# ESP32-S2_VoiceModulator.net
KiCad netlist of a schematic drawn in EAGLE
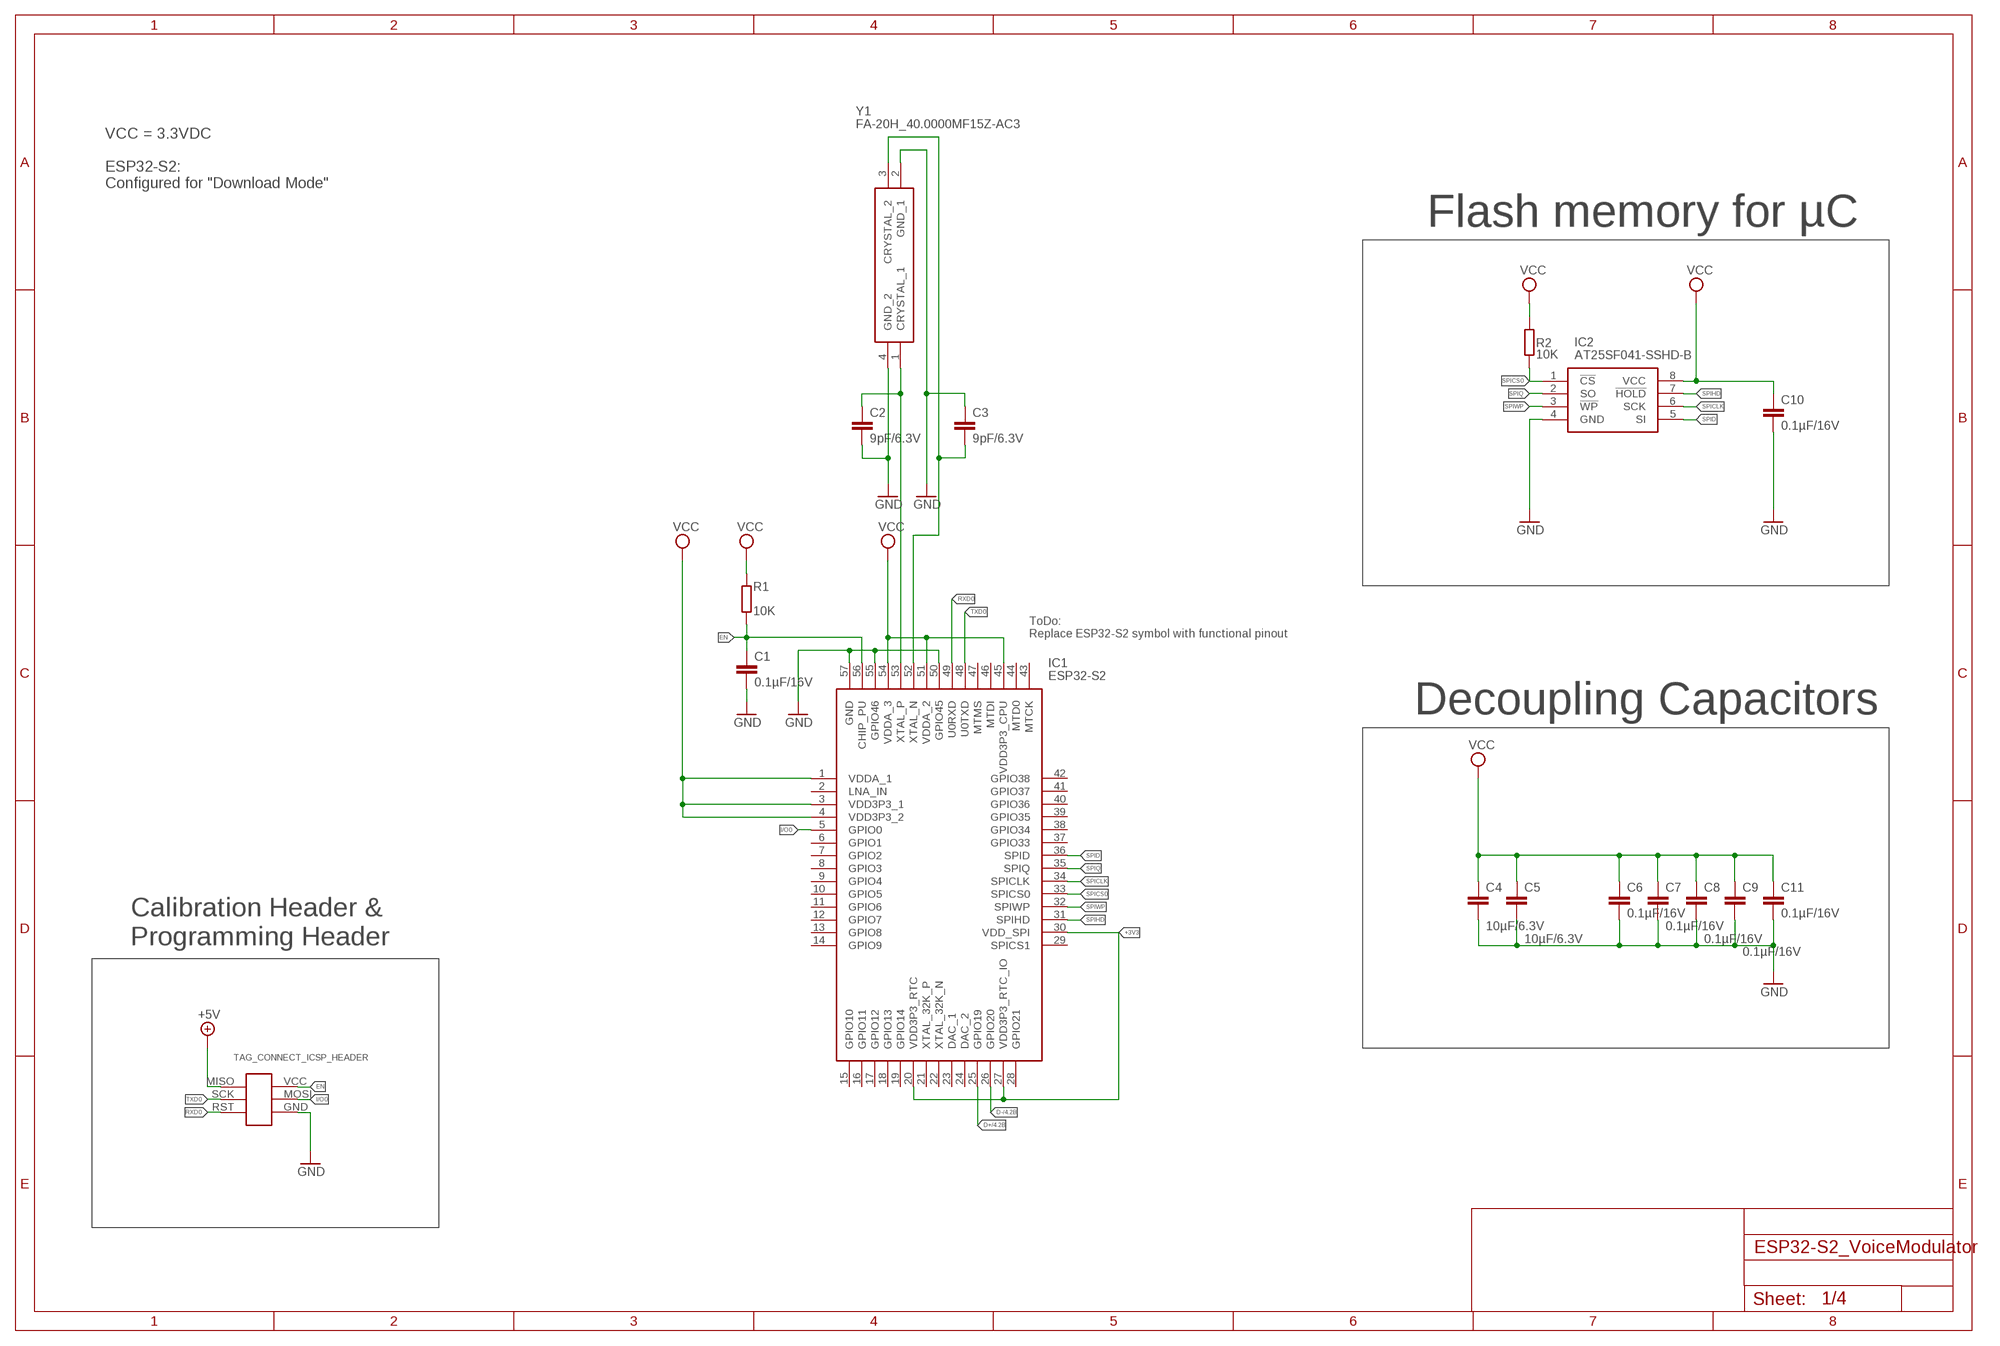
[diagram p0: schematic, sheet 1]
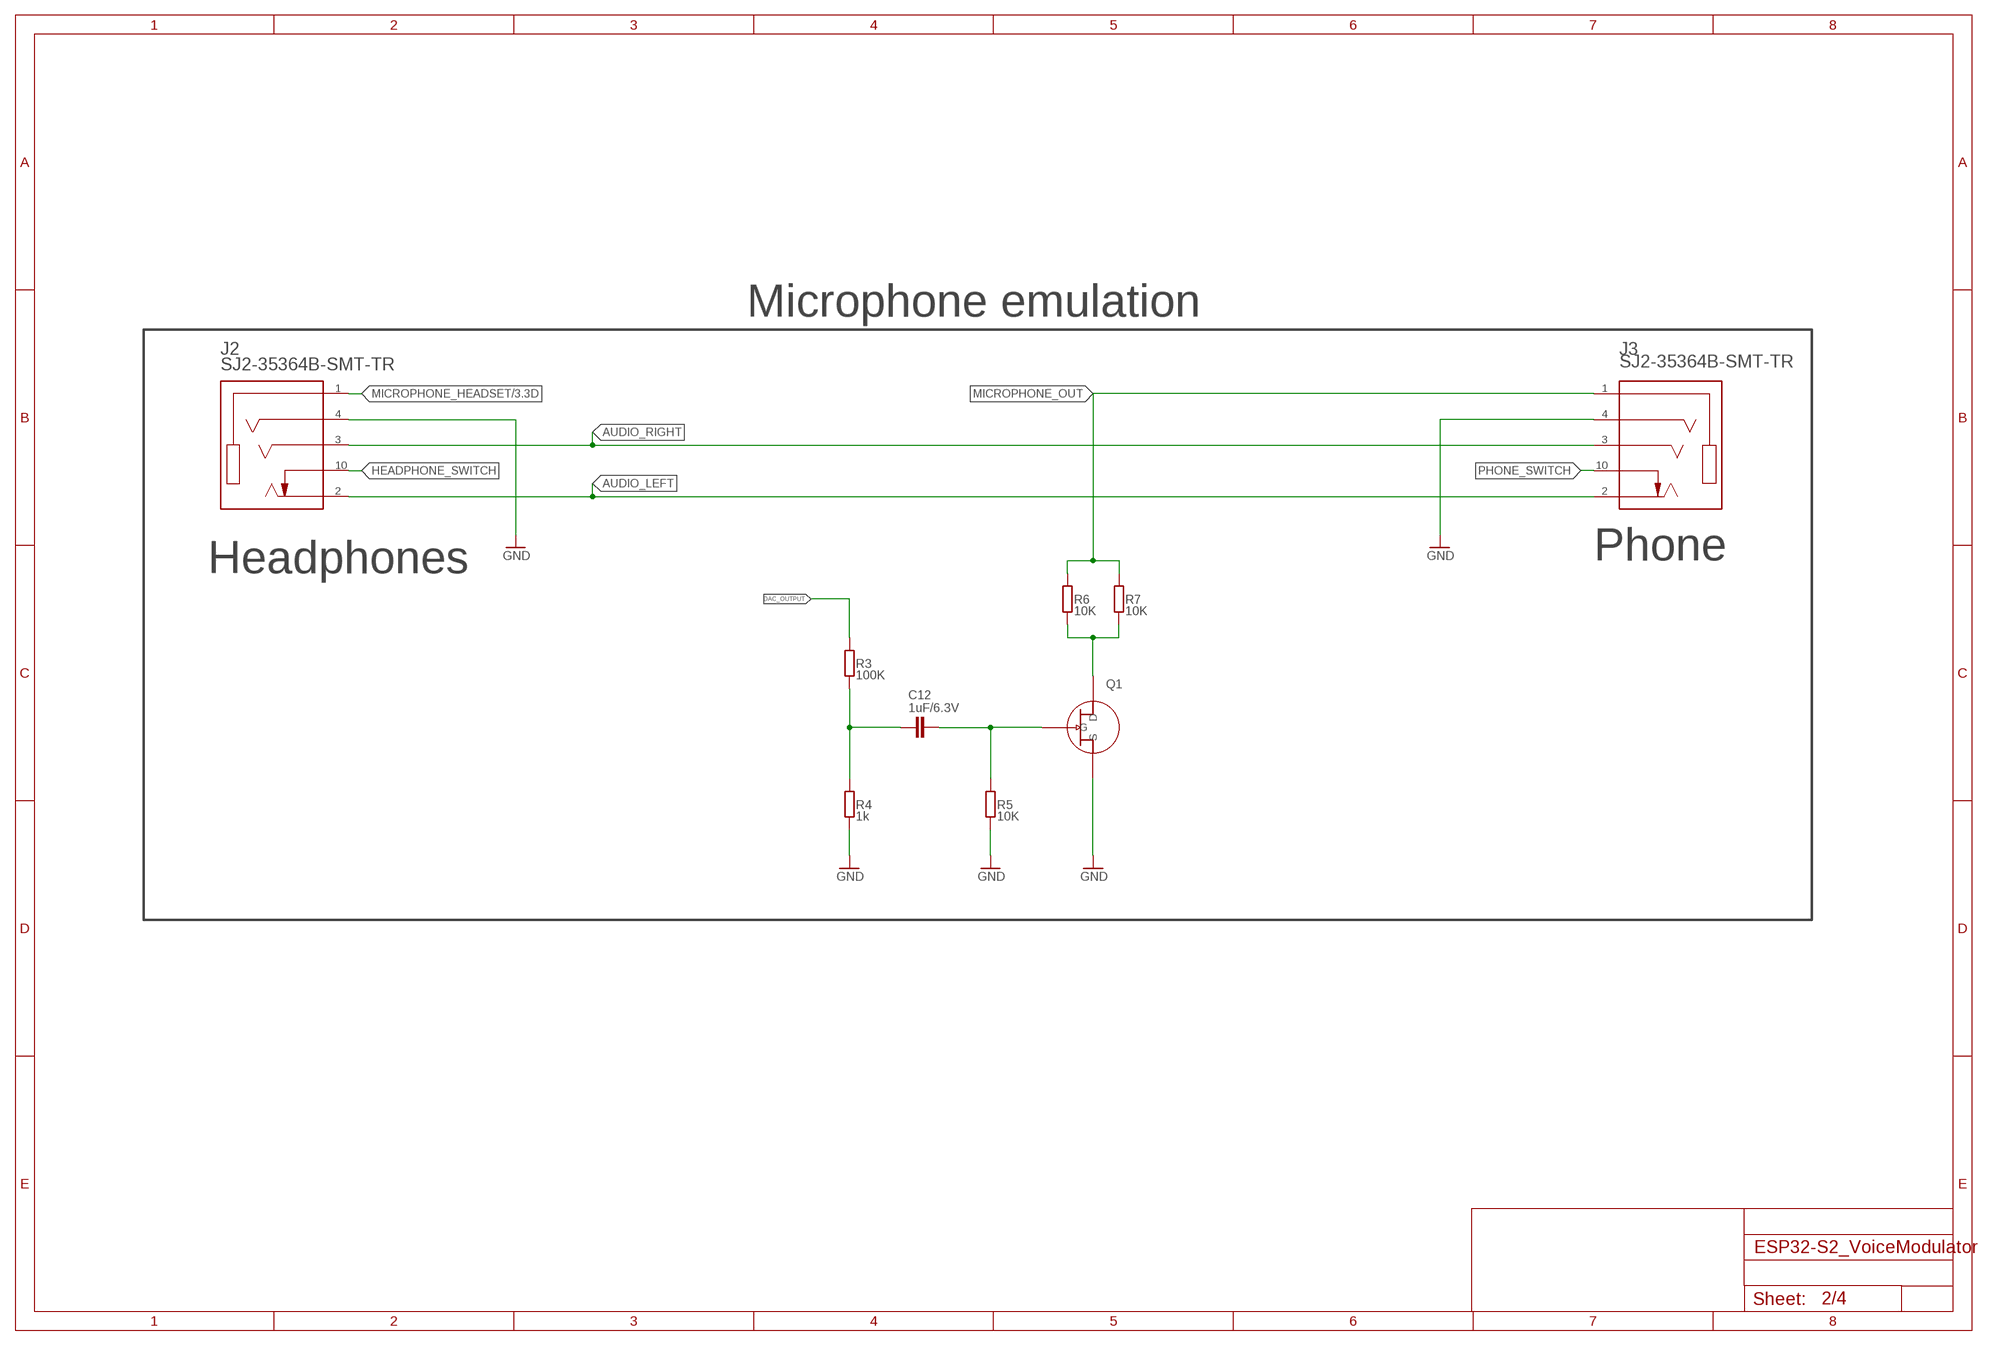
[diagram p1: schematic, sheet 2]
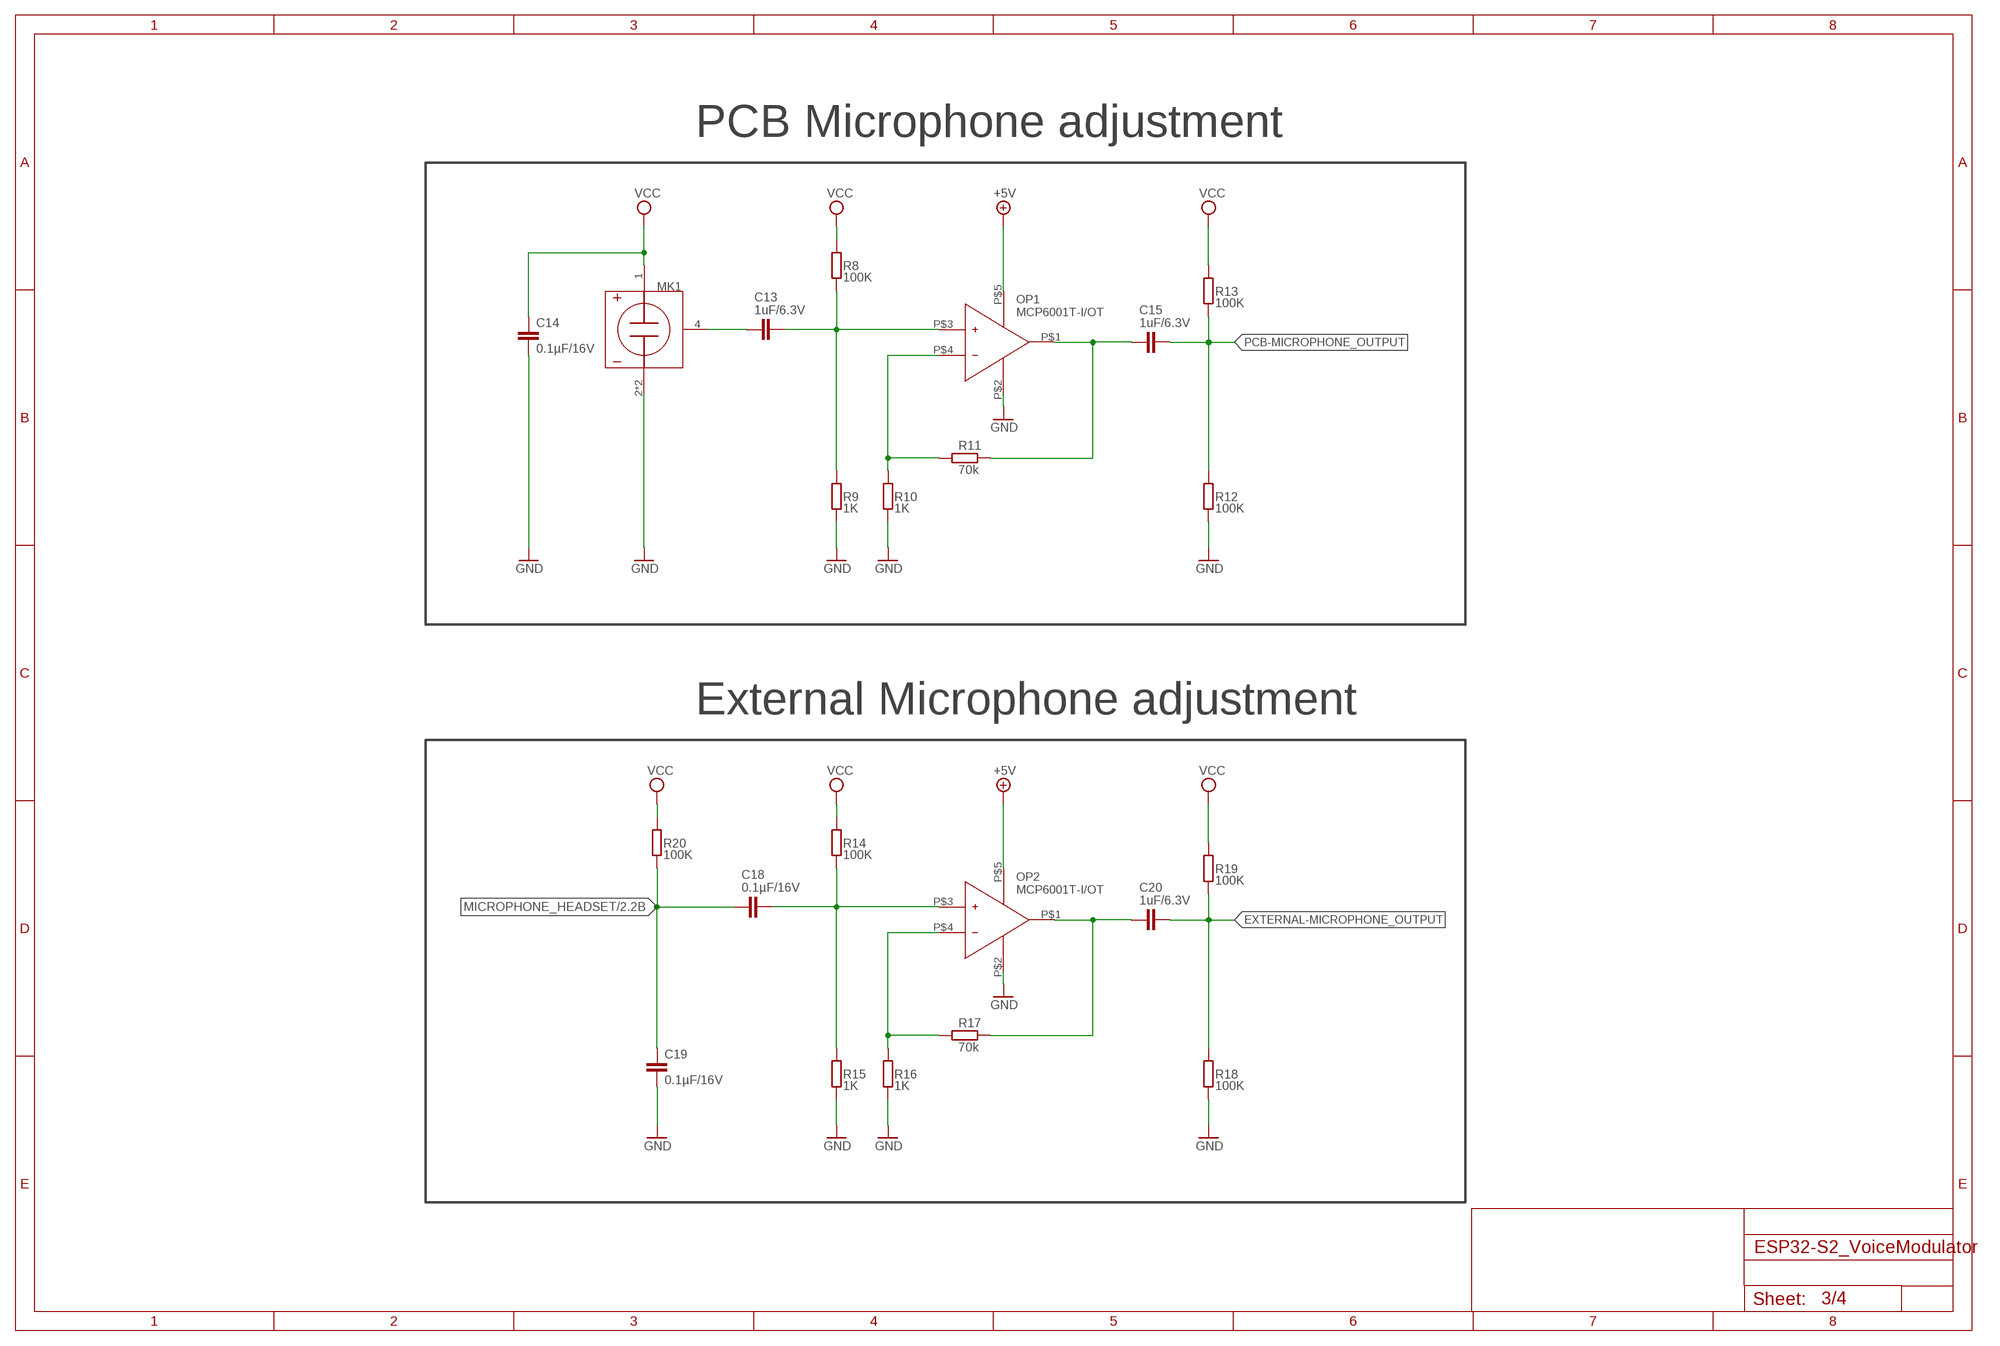
[diagram p2: schematic, sheet 3]
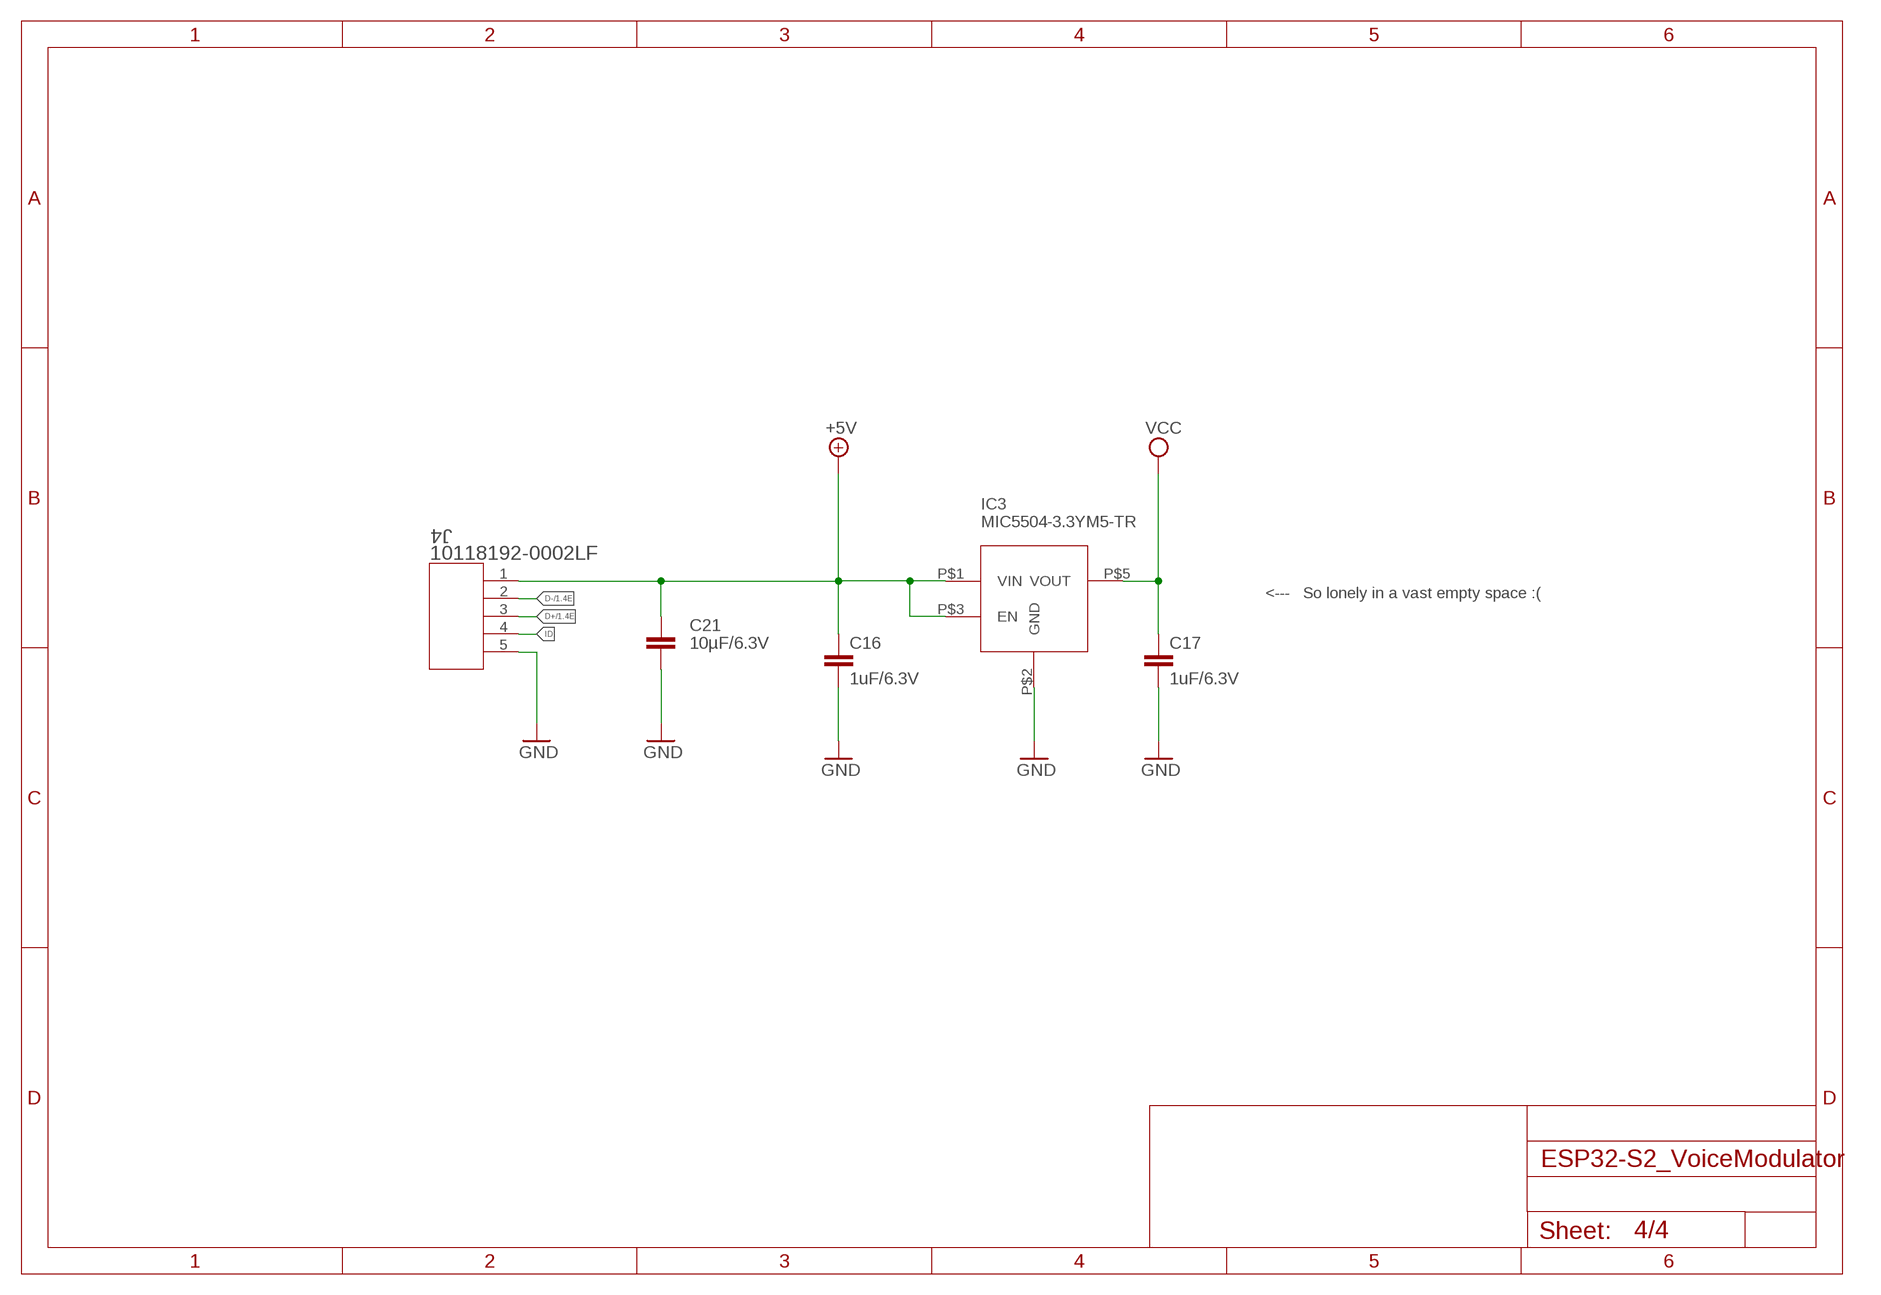
[diagram p3: schematic, sheet 4]

(export (version "E")
  (design (tool "Eeschema 10.0.6"))
  (components
    (comp (ref "C12")
      (value "1uF/6.3V")
      (footprint "eagle-import:C0603")
      (libsource (lib "eagle-import") (part "resistor_348_C-EUC0603"))
    )
    (comp (ref "J2")
      (value "SJ2-35364B-SMT-TR")
      (footprint "eagle-import:SJ2-35364B-SMT-TR")
      (fields (field (name "SPICEPREFIX") "X"))
      (libsource (lib "eagle-import") (part "SJ2-35364B-SMT-TR"))
    )
    (comp (ref "J3")
      (value "SJ2-35364B-SMT-TR")
      (footprint "eagle-import:SJ2-35364B-SMT-TR")
      (libsource (lib "eagle-import") (part "SJ2-35364B-SMT-TR"))
    )
    (comp (ref "Q1")
      (value "CPH3910")
      (footprint "eagle-import:SOT-23-3")
      (libsource (lib "eagle-import") (part "CPH3910"))
    )
    (comp (ref "R3")
      (value "100K")
      (footprint "eagle-import:R0603")
      (libsource (lib "eagle-import") (part "R-EU_R0603"))
    )
    (comp (ref "R4")
      (value "1k")
      (footprint "eagle-import:R0603")
      (libsource (lib "eagle-import") (part "R-EU_R0603"))
    )
    (comp (ref "R5")
      (value "10K")
      (footprint "eagle-import:R0603")
      (libsource (lib "eagle-import") (part "R-EU_R0603"))
    )
    (comp (ref "R6")
      (value "10K")
      (footprint "eagle-import:R0603")
      (libsource (lib "eagle-import") (part "R-EU_R0603"))
    )
    (comp (ref "R7")
      (value "10K")
      (footprint "eagle-import:R0603")
      (libsource (lib "eagle-import") (part "R-EU_R0603"))
    )
    (comp (ref "C1")
      (value "0.1µF/16V")
      (footprint "eagle-import:C0402")
      (libsource (lib "eagle-import") (part "C-EUC0402"))
    )
    (comp (ref "C2")
      (value "9pF/6.3V")
      (footprint "eagle-import:C0603")
      (libsource (lib "eagle-import") (part "C-EUC0603"))
    )
    (comp (ref "C3")
      (value "9pF/6.3V")
      (footprint "eagle-import:C0603")
      (libsource (lib "eagle-import") (part "C-EUC0603"))
    )
    (comp (ref "C4")
      (value "10µF/6.3V")
      (footprint "eagle-import:C0603")
      (libsource (lib "eagle-import") (part "C-EUC0603"))
    )
    (comp (ref "C5")
      (value "10µF/6.3V")
      (footprint "eagle-import:C0603")
      (libsource (lib "eagle-import") (part "C-EUC0603"))
    )
    (comp (ref "C6")
      (value "0.1µF/16V")
      (footprint "eagle-import:C0402")
      (libsource (lib "eagle-import") (part "C-EUC0402"))
    )
    (comp (ref "C7")
      (value "0.1µF/16V")
      (footprint "eagle-import:C0402")
      (libsource (lib "eagle-import") (part "C-EUC0402"))
    )
    (comp (ref "C8")
      (value "0.1µF/16V")
      (footprint "eagle-import:C0402")
      (libsource (lib "eagle-import") (part "C-EUC0402"))
    )
    (comp (ref "C9")
      (value "0.1µF/16V")
      (footprint "eagle-import:C0402")
      (libsource (lib "eagle-import") (part "C-EUC0402"))
    )
    (comp (ref "C10")
      (value "0.1µF/16V")
      (footprint "eagle-import:C0402")
      (libsource (lib "eagle-import") (part "C-EUC0402"))
    )
    (comp (ref "C11")
      (value "0.1µF/16V")
      (footprint "eagle-import:C0402")
      (libsource (lib "eagle-import") (part "C-EUC0402"))
    )
    (comp (ref "IC1")
      (value "ESP32-S2")
      (footprint "eagle-import:QFN40P700X700X90-57N")
      (fields (field (name "MOUSER_PART_NUMBER") "356-ESP32-S2"))
      (libsource (lib "eagle-import") (part "ESP32-S2"))
    )
    (comp (ref "IC2")
      (value "AT25SF041-SSHD-B")
      (footprint "eagle-import:SOIC127P600X175-8N")
      (fields (field (name "MOUSER_PART_NUMBER") "988-AT25SF041-SSHD-B"))
      (libsource (lib "eagle-import") (part "AT25SF041-SSHD-B"))
    )
    (comp (ref "R1")
      (value "10K")
      (footprint "eagle-import:R0603")
      (libsource (lib "eagle-import") (part "R-EU_R0603"))
    )
    (comp (ref "R2")
      (value "10K")
      (footprint "eagle-import:R0603")
      (libsource (lib "eagle-import") (part "R-EU_R0603"))
    )
    (comp (ref "TAG_CONNECT_ICSP_HEADER")
      (value "TAG-CONNECT_PADS")
      (footprint "eagle-import:TAG-CONNECT_PADS")
      (libsource (lib "eagle-import") (part "TAG-CONNECT_PADS"))
    )
    (comp (ref "Y1")
      (value "FA-20H_40.0000MF15Z-AC3")
      (footprint "eagle-import:FA20H160000MF12ZAC3")
      (fields
        (field (name "MANUFACTURER_PART_NUMBER") "FA-20H 40.0000MF15Z-AC3")
        (field (name "MOUSER_PART_NUMBER") "732-FA-20H40F15Z-AC3")
      )
      (libsource (lib "eagle-import") (part "FA-20H_40.0000MF15Z-AC3"))
    )
    (comp (ref "C16")
      (value "1uF/6.3V")
      (footprint "eagle-import:C0603")
      (libsource (lib "eagle-import") (part "resistor_348_C-EUC0603"))
    )
    (comp (ref "C17")
      (value "1uF/6.3V")
      (footprint "eagle-import:C0603")
      (libsource (lib "eagle-import") (part "resistor_348_C-EUC0603"))
    )
    (comp (ref "C21")
      (value "10µF/6.3V")
      (footprint "eagle-import:C0603")
      (libsource (lib "eagle-import") (part "C-EUC0603"))
    )
    (comp (ref "IC3")
      (value "MIC5504-3.3YM5-TR")
      (footprint "eagle-import:SOT-23-5")
      (libsource (lib "eagle-import") (part "MIC5504-3.3YM5-TR"))
    )
    (comp (ref "J4")
      (value "10118192-0002LF")
      (footprint "eagle-import:CONN_10118192-0002LF_AMP")
      (fields (field (name "COPYRIGHT") "Copyright (C) 2018 Accelerated Designs. All rights reserved"))
      (libsource (lib "eagle-import") (part "10118192-0002LF"))
    )
    (comp (ref "C13")
      (value "1uF/6.3V")
      (footprint "eagle-import:C0603")
      (libsource (lib "eagle-import") (part "resistor_348_C-EUC0603"))
    )
    (comp (ref "C14")
      (value "0.1µF/16V")
      (footprint "eagle-import:C0402")
      (libsource (lib "eagle-import") (part "C-EUC0402"))
    )
    (comp (ref "C15")
      (value "1uF/6.3V")
      (footprint "eagle-import:C0603")
      (libsource (lib "eagle-import") (part "resistor_348_C-EUC0603"))
    )
    (comp (ref "C18")
      (value "0.1µF/16V")
      (footprint "eagle-import:C0603")
      (libsource (lib "eagle-import") (part "resistor_348_C-EUC0603"))
    )
    (comp (ref "C19")
      (value "0.1µF/16V")
      (footprint "eagle-import:C0402")
      (libsource (lib "eagle-import") (part "C-EUC0402"))
    )
    (comp (ref "C20")
      (value "1uF/6.3V")
      (footprint "eagle-import:C0603")
      (libsource (lib "eagle-import") (part "resistor_348_C-EUC0603"))
    )
    (comp (ref "MK1")
      (value "WMM7022AT0")
      (footprint "eagle-import:WMM7022AT0")
      (libsource (lib "eagle-import") (part "WMM7022AT0"))
    )
    (comp (ref "OP1")
      (value "MCP6001T-I/OT")
      (footprint "eagle-import:SOT-23-5")
      (libsource (lib "eagle-import") (part "MCP6001T-I/OT"))
    )
    (comp (ref "OP2")
      (value "MCP6001T-I/OT")
      (footprint "eagle-import:SOT-23-5")
      (libsource (lib "eagle-import") (part "MCP6001T-I/OT"))
    )
    (comp (ref "R8")
      (value "100K")
      (footprint "eagle-import:R0603")
      (libsource (lib "eagle-import") (part "R-EU_R0603"))
    )
    (comp (ref "R9")
      (value "1K")
      (footprint "eagle-import:R0603")
      (libsource (lib "eagle-import") (part "R-EU_R0603"))
    )
    (comp (ref "R10")
      (value "1K")
      (footprint "eagle-import:R0603")
      (libsource (lib "eagle-import") (part "R-EU_R0603"))
    )
    (comp (ref "R11")
      (value "70k")
      (footprint "eagle-import:R0603")
      (libsource (lib "eagle-import") (part "R-EU_R0603"))
    )
    (comp (ref "R12")
      (value "100K")
      (footprint "eagle-import:R0603")
      (libsource (lib "eagle-import") (part "R-EU_R0603"))
    )
    (comp (ref "R13")
      (value "100K")
      (footprint "eagle-import:R0603")
      (libsource (lib "eagle-import") (part "R-EU_R0603"))
    )
    (comp (ref "R14")
      (value "100K")
      (footprint "eagle-import:R0603")
      (libsource (lib "eagle-import") (part "R-EU_R0603"))
    )
    (comp (ref "R15")
      (value "1K")
      (footprint "eagle-import:R0603")
      (libsource (lib "eagle-import") (part "R-EU_R0603"))
    )
    (comp (ref "R16")
      (value "1K")
      (footprint "eagle-import:R0603")
      (libsource (lib "eagle-import") (part "R-EU_R0603"))
    )
    (comp (ref "R17")
      (value "70k")
      (footprint "eagle-import:R0603")
      (libsource (lib "eagle-import") (part "R-EU_R0603"))
    )
    (comp (ref "R18")
      (value "100K")
      (footprint "eagle-import:R0603")
      (libsource (lib "eagle-import") (part "R-EU_R0603"))
    )
    (comp (ref "R19")
      (value "100K")
      (footprint "eagle-import:R0603")
      (libsource (lib "eagle-import") (part "R-EU_R0603"))
    )
    (comp (ref "R20")
      (value "100K")
      (footprint "eagle-import:R0603")
      (libsource (lib "eagle-import") (part "R-EU_R0603"))
    )
  )
  (nets
    (net (code "1") (name "+3V3") (class "Default")
      (node (ref "IC1") (pin "20") (pinfunction "VDD3P3_RTC_20") (pintype "bidirectional"))
      (node (ref "IC1") (pin "27") (pinfunction "VDD3P3_RTC_IO_27") (pintype "bidirectional"))
      (node (ref "IC1") (pin "30") (pinfunction "VDD_SPI_30") (pintype "bidirectional"))
    )
    (net (code "2") (name "+5V") (class "Default")
      (node (ref "C16") (pin "1") (pinfunction "1_1") (pintype "passive"))
      (node (ref "C21") (pin "1") (pinfunction "1_1") (pintype "passive"))
      (node (ref "IC3") (pin "P$1") (pinfunction "VIN_P$1") (pintype "power_in"))
      (node (ref "IC3") (pin "P$3") (pinfunction "EN_P$3") (pintype "bidirectional"))
      (node (ref "J4") (pin "1") (pinfunction "1_1") (pintype "passive"))
      (node (ref "OP1") (pin "P$5") (pinfunction "VDD_P$5") (pintype "power_in"))
      (node (ref "OP2") (pin "P$5") (pinfunction "VDD_P$5") (pintype "power_in"))
      (node (ref "TAG_CONNECT_ICSP_HEADER") (pin "MISO") (pinfunction "MISO_MISO") (pintype "bidirectional"))
    )
    (net (code "3") (name "AUDIO_LEFT") (class "Default")
      (node (ref "J2") (pin "2") (pinfunction "2_2") (pintype "passive"))
      (node (ref "J3") (pin "2") (pinfunction "2_2") (pintype "passive"))
    )
    (net (code "4") (name "AUDIO_RIGHT") (class "Default")
      (node (ref "J2") (pin "3") (pinfunction "3_3") (pintype "passive"))
      (node (ref "J3") (pin "3") (pinfunction "3_3") (pintype "passive"))
    )
    (net (code "5") (name "D+") (class "Default")
      (node (ref "IC1") (pin "25") (pinfunction "GPIO19_25") (pintype "bidirectional"))
      (node (ref "J4") (pin "3") (pinfunction "3_3") (pintype "passive"))
    )
    (net (code "6") (name "D-") (class "Default")
      (node (ref "IC1") (pin "26") (pinfunction "GPIO20_26") (pintype "bidirectional"))
      (node (ref "J4") (pin "2") (pinfunction "2_2") (pintype "passive"))
    )
    (net (code "7") (name "DAC_OUTPUT") (class "Default")
      (node (ref "R3") (pin "2") (pinfunction "2_2") (pintype "passive"))
    )
    (net (code "8") (name "EN") (class "Default")
      (node (ref "C1") (pin "1") (pinfunction "1_1") (pintype "passive"))
      (node (ref "IC1") (pin "56") (pinfunction "CHIP_PU_56") (pintype "bidirectional"))
      (node (ref "R1") (pin "1") (pinfunction "1_1") (pintype "passive"))
      (node (ref "TAG_CONNECT_ICSP_HEADER") (pin "VCC") (pinfunction "VCC_VCC") (pintype "bidirectional"))
    )
    (net (code "9") (name "EXTERNAL-MICROPHONE_OUTPUT") (class "Default")
      (node (ref "C20") (pin "2") (pinfunction "2_2") (pintype "passive"))
      (node (ref "R18") (pin "2") (pinfunction "2_2") (pintype "passive"))
      (node (ref "R19") (pin "1") (pinfunction "1_1") (pintype "passive"))
    )
    (net (code "10") (name "GND") (class "Default")
      (node (ref "C1") (pin "2") (pinfunction "2_2") (pintype "passive"))
      (node (ref "C10") (pin "2") (pinfunction "2_2") (pintype "passive"))
      (node (ref "C11") (pin "2") (pinfunction "2_2") (pintype "passive"))
      (node (ref "C14") (pin "2") (pinfunction "2_2") (pintype "passive"))
      (node (ref "C16") (pin "2") (pinfunction "2_2") (pintype "passive"))
      (node (ref "C17") (pin "2") (pinfunction "2_2") (pintype "passive"))
      (node (ref "C19") (pin "2") (pinfunction "2_2") (pintype "passive"))
      (node (ref "C2") (pin "2") (pinfunction "2_2") (pintype "passive"))
      (node (ref "C21") (pin "2") (pinfunction "2_2") (pintype "passive"))
      (node (ref "C3") (pin "1") (pinfunction "1_1") (pintype "passive"))
      (node (ref "C4") (pin "2") (pinfunction "2_2") (pintype "passive"))
      (node (ref "C5") (pin "2") (pinfunction "2_2") (pintype "passive"))
      (node (ref "C6") (pin "2") (pinfunction "2_2") (pintype "passive"))
      (node (ref "C7") (pin "2") (pinfunction "2_2") (pintype "passive"))
      (node (ref "C8") (pin "2") (pinfunction "2_2") (pintype "passive"))
      (node (ref "C9") (pin "2") (pinfunction "2_2") (pintype "passive"))
      (node (ref "IC1") (pin "50") (pinfunction "GPIO45_50") (pintype "bidirectional"))
      (node (ref "IC1") (pin "55") (pinfunction "GPIO46_55") (pintype "bidirectional"))
      (node (ref "IC1") (pin "57") (pinfunction "GND_57") (pintype "bidirectional"))
      (node (ref "IC2") (pin "4") (pinfunction "GND_4") (pintype "bidirectional"))
      (node (ref "IC3") (pin "P$2") (pinfunction "GND_P$2") (pintype "bidirectional"))
      (node (ref "J2") (pin "4") (pinfunction "4_4") (pintype "passive"))
      (node (ref "J3") (pin "4") (pinfunction "4_4") (pintype "passive"))
      (node (ref "J4") (pin "5") (pinfunction "5_5") (pintype "passive"))
      (node (ref "MK1") (pin "2") (pinfunction "GND_2") (pintype "bidirectional"))
      (node (ref "MK1") (pin "3") (pinfunction "GND_3") (pintype "bidirectional"))
      (node (ref "OP1") (pin "P$2") (pinfunction "VSS_P$2") (pintype "bidirectional"))
      (node (ref "OP2") (pin "P$2") (pinfunction "VSS_P$2") (pintype "bidirectional"))
      (node (ref "Q1") (pin "P$1") (pinfunction "S_P$1") (pintype "bidirectional"))
      (node (ref "R10") (pin "1") (pinfunction "1_1") (pintype "passive"))
      (node (ref "R12") (pin "1") (pinfunction "1_1") (pintype "passive"))
      (node (ref "R15") (pin "1") (pinfunction "1_1") (pintype "passive"))
      (node (ref "R16") (pin "1") (pinfunction "1_1") (pintype "passive"))
      (node (ref "R18") (pin "1") (pinfunction "1_1") (pintype "passive"))
      (node (ref "R4") (pin "1") (pinfunction "1_1") (pintype "passive"))
      (node (ref "R5") (pin "2") (pinfunction "2_2") (pintype "passive"))
      (node (ref "R9") (pin "1") (pinfunction "1_1") (pintype "passive"))
      (node (ref "TAG_CONNECT_ICSP_HEADER") (pin "GND") (pinfunction "GND_GND") (pintype "bidirectional"))
      (node (ref "Y1") (pin "2") (pinfunction "GND_1_2") (pintype "bidirectional"))
      (node (ref "Y1") (pin "4") (pinfunction "GND_2_4") (pintype "bidirectional"))
    )
    (net (code "11") (name "HEADPHONE_SWITCH") (class "Default")
      (node (ref "J2") (pin "10") (pinfunction "10_10") (pintype "passive"))
    )
    (net (code "12") (name "ID") (class "Default")
      (node (ref "J4") (pin "4") (pinfunction "4_4") (pintype "passive"))
    )
    (net (code "13") (name "I{slash}O0") (class "Default")
      (node (ref "IC1") (pin "5") (pinfunction "GPIO0_5") (pintype "bidirectional"))
      (node (ref "TAG_CONNECT_ICSP_HEADER") (pin "MOSI") (pinfunction "MOSI_MOSI") (pintype "bidirectional"))
    )
    (net (code "14") (name "MICROPHONE_HEADSET") (class "Default")
      (node (ref "C18") (pin "1") (pinfunction "1_1") (pintype "passive"))
      (node (ref "C19") (pin "1") (pinfunction "1_1") (pintype "passive"))
      (node (ref "J2") (pin "1") (pinfunction "1_1") (pintype "passive"))
      (node (ref "R20") (pin "1") (pinfunction "1_1") (pintype "passive"))
    )
    (net (code "15") (name "MICROPHONE_OUT") (class "Default")
      (node (ref "J3") (pin "1") (pinfunction "1_1") (pintype "passive"))
      (node (ref "R6") (pin "1") (pinfunction "1_1") (pintype "passive"))
      (node (ref "R7") (pin "2") (pinfunction "2_2") (pintype "passive"))
    )
    (net (code "16") (name "Net-(C12-Pad1)") (class "Default")
      (node (ref "C12") (pin "1") (pinfunction "1_1") (pintype "passive"))
      (node (ref "R3") (pin "1") (pinfunction "1_1") (pintype "passive"))
      (node (ref "R4") (pin "2") (pinfunction "2_2") (pintype "passive"))
    )
    (net (code "17") (name "Net-(IC1-XTAL_N)") (class "Default")
      (node (ref "C3") (pin "2") (pinfunction "2_2") (pintype "passive"))
      (node (ref "IC1") (pin "52") (pinfunction "XTAL_N_52") (pintype "bidirectional"))
      (node (ref "Y1") (pin "3") (pinfunction "CRYSTAL_2_3") (pintype "bidirectional"))
    )
    (net (code "18") (name "Net-(IC1-XTAL_P)") (class "Default")
      (node (ref "C2") (pin "1") (pinfunction "1_1") (pintype "passive"))
      (node (ref "IC1") (pin "53") (pinfunction "XTAL_P_53") (pintype "bidirectional"))
      (node (ref "Y1") (pin "1") (pinfunction "CRYSTAL_1_1") (pintype "bidirectional"))
    )
    (net (code "19") (name "Net-(MK1-OUT)") (class "Default")
      (node (ref "C13") (pin "1") (pinfunction "1_1") (pintype "passive"))
      (node (ref "MK1") (pin "4") (pinfunction "OUT_4") (pintype "output"))
    )
    (net (code "20") (name "Net-(OP1-V+)") (class "Default")
      (node (ref "C13") (pin "2") (pinfunction "2_2") (pintype "passive"))
      (node (ref "OP1") (pin "P$3") (pinfunction "V+_P$3") (pintype "bidirectional"))
      (node (ref "R8") (pin "1") (pinfunction "1_1") (pintype "passive"))
      (node (ref "R9") (pin "2") (pinfunction "2_2") (pintype "passive"))
    )
    (net (code "21") (name "Net-(OP1-V-)") (class "Default")
      (node (ref "OP1") (pin "P$4") (pinfunction "V-_P$4") (pintype "bidirectional"))
      (node (ref "R10") (pin "2") (pinfunction "2_2") (pintype "passive"))
      (node (ref "R11") (pin "2") (pinfunction "2_2") (pintype "passive"))
    )
    (net (code "22") (name "Net-(OP1-VOUT)") (class "Default")
      (node (ref "C15") (pin "1") (pinfunction "1_1") (pintype "passive"))
      (node (ref "OP1") (pin "P$1") (pinfunction "VOUT_P$1") (pintype "output"))
      (node (ref "R11") (pin "1") (pinfunction "1_1") (pintype "passive"))
    )
    (net (code "23") (name "Net-(OP2-V+)") (class "Default")
      (node (ref "C18") (pin "2") (pinfunction "2_2") (pintype "passive"))
      (node (ref "OP2") (pin "P$3") (pinfunction "V+_P$3") (pintype "bidirectional"))
      (node (ref "R14") (pin "1") (pinfunction "1_1") (pintype "passive"))
      (node (ref "R15") (pin "2") (pinfunction "2_2") (pintype "passive"))
    )
    (net (code "24") (name "Net-(OP2-V-)") (class "Default")
      (node (ref "OP2") (pin "P$4") (pinfunction "V-_P$4") (pintype "bidirectional"))
      (node (ref "R16") (pin "2") (pinfunction "2_2") (pintype "passive"))
      (node (ref "R17") (pin "2") (pinfunction "2_2") (pintype "passive"))
    )
    (net (code "25") (name "Net-(OP2-VOUT)") (class "Default")
      (node (ref "C20") (pin "1") (pinfunction "1_1") (pintype "passive"))
      (node (ref "OP2") (pin "P$1") (pinfunction "VOUT_P$1") (pintype "output"))
      (node (ref "R17") (pin "1") (pinfunction "1_1") (pintype "passive"))
    )
    (net (code "26") (name "Net-(Q1-D)") (class "Default")
      (node (ref "Q1") (pin "P$2") (pinfunction "D_P$2") (pintype "bidirectional"))
      (node (ref "R6") (pin "2") (pinfunction "2_2") (pintype "passive"))
      (node (ref "R7") (pin "1") (pinfunction "1_1") (pintype "passive"))
    )
    (net (code "27") (name "Net-(Q1-G)") (class "Default")
      (node (ref "C12") (pin "2") (pinfunction "2_2") (pintype "passive"))
      (node (ref "Q1") (pin "P$3") (pinfunction "G_P$3") (pintype "bidirectional"))
      (node (ref "R5") (pin "1") (pinfunction "1_1") (pintype "passive"))
    )
    (net (code "28") (name "PCB-MICROPHONE_OUTPUT") (class "Default")
      (node (ref "C15") (pin "2") (pinfunction "2_2") (pintype "passive"))
      (node (ref "R12") (pin "2") (pinfunction "2_2") (pintype "passive"))
      (node (ref "R13") (pin "1") (pinfunction "1_1") (pintype "passive"))
    )
    (net (code "29") (name "PHONE_SWITCH") (class "Default")
      (node (ref "J3") (pin "10") (pinfunction "10_10") (pintype "passive"))
    )
    (net (code "30") (name "RXD0") (class "Default")
      (node (ref "IC1") (pin "49") (pinfunction "U0RXD_49") (pintype "bidirectional"))
      (node (ref "TAG_CONNECT_ICSP_HEADER") (pin "RST") (pinfunction "RST_RST") (pintype "bidirectional"))
    )
    (net (code "31") (name "SPICLK") (class "Default")
      (node (ref "IC1") (pin "34") (pinfunction "SPICLK_34") (pintype "bidirectional"))
      (node (ref "IC2") (pin "6") (pinfunction "SCK_6") (pintype "bidirectional"))
    )
    (net (code "32") (name "SPICS0") (class "Default")
      (node (ref "IC1") (pin "33") (pinfunction "SPICS0_33") (pintype "bidirectional"))
      (node (ref "IC2") (pin "1") (pinfunction "~{CS}_1") (pintype "bidirectional"))
      (node (ref "R2") (pin "1") (pinfunction "1_1") (pintype "passive"))
    )
    (net (code "33") (name "SPID") (class "Default")
      (node (ref "IC1") (pin "36") (pinfunction "SPID_36") (pintype "bidirectional"))
      (node (ref "IC2") (pin "5") (pinfunction "SI_5") (pintype "bidirectional"))
    )
    (net (code "34") (name "SPIHD") (class "Default")
      (node (ref "IC1") (pin "31") (pinfunction "SPIHD_31") (pintype "bidirectional"))
      (node (ref "IC2") (pin "7") (pinfunction "~{HOLD}_7") (pintype "bidirectional"))
    )
    (net (code "35") (name "SPIQ") (class "Default")
      (node (ref "IC1") (pin "35") (pinfunction "SPIQ_35") (pintype "bidirectional"))
      (node (ref "IC2") (pin "2") (pinfunction "SO_2") (pintype "bidirectional"))
    )
    (net (code "36") (name "SPIWP") (class "Default")
      (node (ref "IC1") (pin "32") (pinfunction "SPIWP_32") (pintype "bidirectional"))
      (node (ref "IC2") (pin "3") (pinfunction "~{WP}_3") (pintype "bidirectional"))
    )
    (net (code "37") (name "TXD0") (class "Default")
      (node (ref "IC1") (pin "48") (pinfunction "U0TXD_48") (pintype "bidirectional"))
      (node (ref "TAG_CONNECT_ICSP_HEADER") (pin "SCK") (pinfunction "SCK_SCK") (pintype "bidirectional"))
    )
    (net (code "38") (name "VCC") (class "Default")
      (node (ref "C10") (pin "1") (pinfunction "1_1") (pintype "passive"))
      (node (ref "C11") (pin "1") (pinfunction "1_1") (pintype "passive"))
      (node (ref "C14") (pin "1") (pinfunction "1_1") (pintype "passive"))
      (node (ref "C17") (pin "1") (pinfunction "1_1") (pintype "passive"))
      (node (ref "C4") (pin "1") (pinfunction "1_1") (pintype "passive"))
      (node (ref "C5") (pin "1") (pinfunction "1_1") (pintype "passive"))
      (node (ref "C6") (pin "1") (pinfunction "1_1") (pintype "passive"))
      (node (ref "C7") (pin "1") (pinfunction "1_1") (pintype "passive"))
      (node (ref "C8") (pin "1") (pinfunction "1_1") (pintype "passive"))
      (node (ref "C9") (pin "1") (pinfunction "1_1") (pintype "passive"))
      (node (ref "IC1") (pin "1") (pinfunction "VDDA_1_1") (pintype "bidirectional"))
      (node (ref "IC1") (pin "3") (pinfunction "VDD3P3_1_3") (pintype "bidirectional"))
      (node (ref "IC1") (pin "4") (pinfunction "VDD3P3_2_4") (pintype "bidirectional"))
      (node (ref "IC1") (pin "45") (pinfunction "VDD3P3_CPU_45") (pintype "bidirectional"))
      (node (ref "IC1") (pin "51") (pinfunction "VDDA_2_51") (pintype "bidirectional"))
      (node (ref "IC1") (pin "54") (pinfunction "VDDA_3_54") (pintype "bidirectional"))
      (node (ref "IC2") (pin "8") (pinfunction "VCC_8") (pintype "bidirectional"))
      (node (ref "IC3") (pin "P$5") (pinfunction "VOUT_P$5") (pintype "output"))
      (node (ref "MK1") (pin "1") (pinfunction "VDD_1") (pintype "power_in"))
      (node (ref "R1") (pin "2") (pinfunction "2_2") (pintype "passive"))
      (node (ref "R13") (pin "2") (pinfunction "2_2") (pintype "passive"))
      (node (ref "R14") (pin "2") (pinfunction "2_2") (pintype "passive"))
      (node (ref "R19") (pin "2") (pinfunction "2_2") (pintype "passive"))
      (node (ref "R2") (pin "2") (pinfunction "2_2") (pintype "passive"))
      (node (ref "R20") (pin "2") (pinfunction "2_2") (pintype "passive"))
      (node (ref "R8") (pin "2") (pinfunction "2_2") (pintype "passive"))
    )
    (net (code "39") (name "unconnected-(IC1-DAC_1-Pad23)") (class "Default")
      (node (ref "IC1") (pin "23") (pinfunction "DAC_1_23") (pintype "bidirectional"))
    )
    (net (code "40") (name "unconnected-(IC1-DAC_2-Pad24)") (class "Default")
      (node (ref "IC1") (pin "24") (pinfunction "DAC_2_24") (pintype "bidirectional"))
    )
    (net (code "41") (name "unconnected-(IC1-GPIO1-Pad6)") (class "Default")
      (node (ref "IC1") (pin "6") (pinfunction "GPIO1_6") (pintype "bidirectional"))
    )
    (net (code "42") (name "unconnected-(IC1-GPIO2-Pad7)") (class "Default")
      (node (ref "IC1") (pin "7") (pinfunction "GPIO2_7") (pintype "bidirectional"))
    )
    (net (code "43") (name "unconnected-(IC1-GPIO3-Pad8)") (class "Default")
      (node (ref "IC1") (pin "8") (pinfunction "GPIO3_8") (pintype "bidirectional"))
    )
    (net (code "44") (name "unconnected-(IC1-GPIO4-Pad9)") (class "Default")
      (node (ref "IC1") (pin "9") (pinfunction "GPIO4_9") (pintype "bidirectional"))
    )
    (net (code "45") (name "unconnected-(IC1-GPIO5-Pad10)") (class "Default")
      (node (ref "IC1") (pin "10") (pinfunction "GPIO5_10") (pintype "bidirectional"))
    )
    (net (code "46") (name "unconnected-(IC1-GPIO6-Pad11)") (class "Default")
      (node (ref "IC1") (pin "11") (pinfunction "GPIO6_11") (pintype "bidirectional"))
    )
    (net (code "47") (name "unconnected-(IC1-GPIO7-Pad12)") (class "Default")
      (node (ref "IC1") (pin "12") (pinfunction "GPIO7_12") (pintype "bidirectional"))
    )
    (net (code "48") (name "unconnected-(IC1-GPIO8-Pad13)") (class "Default")
      (node (ref "IC1") (pin "13") (pinfunction "GPIO8_13") (pintype "bidirectional"))
    )
    (net (code "49") (name "unconnected-(IC1-GPIO9-Pad14)") (class "Default")
      (node (ref "IC1") (pin "14") (pinfunction "GPIO9_14") (pintype "bidirectional"))
    )
    (net (code "50") (name "unconnected-(IC1-GPIO10-Pad15)") (class "Default")
      (node (ref "IC1") (pin "15") (pinfunction "GPIO10_15") (pintype "bidirectional"))
    )
    (net (code "51") (name "unconnected-(IC1-GPIO11-Pad16)") (class "Default")
      (node (ref "IC1") (pin "16") (pinfunction "GPIO11_16") (pintype "bidirectional"))
    )
    (net (code "52") (name "unconnected-(IC1-GPIO12-Pad17)") (class "Default")
      (node (ref "IC1") (pin "17") (pinfunction "GPIO12_17") (pintype "bidirectional"))
    )
    (net (code "53") (name "unconnected-(IC1-GPIO13-Pad18)") (class "Default")
      (node (ref "IC1") (pin "18") (pinfunction "GPIO13_18") (pintype "bidirectional"))
    )
    (net (code "54") (name "unconnected-(IC1-GPIO14-Pad19)") (class "Default")
      (node (ref "IC1") (pin "19") (pinfunction "GPIO14_19") (pintype "bidirectional"))
    )
    (net (code "55") (name "unconnected-(IC1-GPIO21-Pad28)") (class "Default")
      (node (ref "IC1") (pin "28") (pinfunction "GPIO21_28") (pintype "bidirectional"))
    )
    (net (code "56") (name "unconnected-(IC1-GPIO33-Pad37)") (class "Default")
      (node (ref "IC1") (pin "37") (pinfunction "GPIO33_37") (pintype "bidirectional"))
    )
    (net (code "57") (name "unconnected-(IC1-GPIO34-Pad38)") (class "Default")
      (node (ref "IC1") (pin "38") (pinfunction "GPIO34_38") (pintype "bidirectional"))
    )
    (net (code "58") (name "unconnected-(IC1-GPIO35-Pad39)") (class "Default")
      (node (ref "IC1") (pin "39") (pinfunction "GPIO35_39") (pintype "bidirectional"))
    )
    (net (code "59") (name "unconnected-(IC1-GPIO36-Pad40)") (class "Default")
      (node (ref "IC1") (pin "40") (pinfunction "GPIO36_40") (pintype "bidirectional"))
    )
    (net (code "60") (name "unconnected-(IC1-GPIO37-Pad41)") (class "Default")
      (node (ref "IC1") (pin "41") (pinfunction "GPIO37_41") (pintype "bidirectional"))
    )
    (net (code "61") (name "unconnected-(IC1-GPIO38-Pad42)") (class "Default")
      (node (ref "IC1") (pin "42") (pinfunction "GPIO38_42") (pintype "bidirectional"))
    )
    (net (code "62") (name "unconnected-(IC1-LNA_IN-Pad2)") (class "Default")
      (node (ref "IC1") (pin "2") (pinfunction "LNA_IN_2") (pintype "bidirectional"))
    )
    (net (code "63") (name "unconnected-(IC1-MTCK-Pad43)") (class "Default")
      (node (ref "IC1") (pin "43") (pinfunction "MTCK_43") (pintype "bidirectional"))
    )
    (net (code "64") (name "unconnected-(IC1-MTD0-Pad44)") (class "Default")
      (node (ref "IC1") (pin "44") (pinfunction "MTD0_44") (pintype "bidirectional"))
    )
    (net (code "65") (name "unconnected-(IC1-MTDI-Pad46)") (class "Default")
      (node (ref "IC1") (pin "46") (pinfunction "MTDI_46") (pintype "bidirectional"))
    )
    (net (code "66") (name "unconnected-(IC1-MTMS-Pad47)") (class "Default")
      (node (ref "IC1") (pin "47") (pinfunction "MTMS_47") (pintype "bidirectional"))
    )
    (net (code "67") (name "unconnected-(IC1-SPICS1-Pad29)") (class "Default")
      (node (ref "IC1") (pin "29") (pinfunction "SPICS1_29") (pintype "bidirectional"))
    )
    (net (code "68") (name "unconnected-(IC1-XTAL_32K_N-Pad22)") (class "Default")
      (node (ref "IC1") (pin "22") (pinfunction "XTAL_32K_N_22") (pintype "bidirectional"))
    )
    (net (code "69") (name "unconnected-(IC1-XTAL_32K_P-Pad21)") (class "Default")
      (node (ref "IC1") (pin "21") (pinfunction "XTAL_32K_P_21") (pintype "bidirectional"))
    )
  )
)
